# IO_Peripherals.net
KiCad netlist of a schematic drawn in Altium Designer
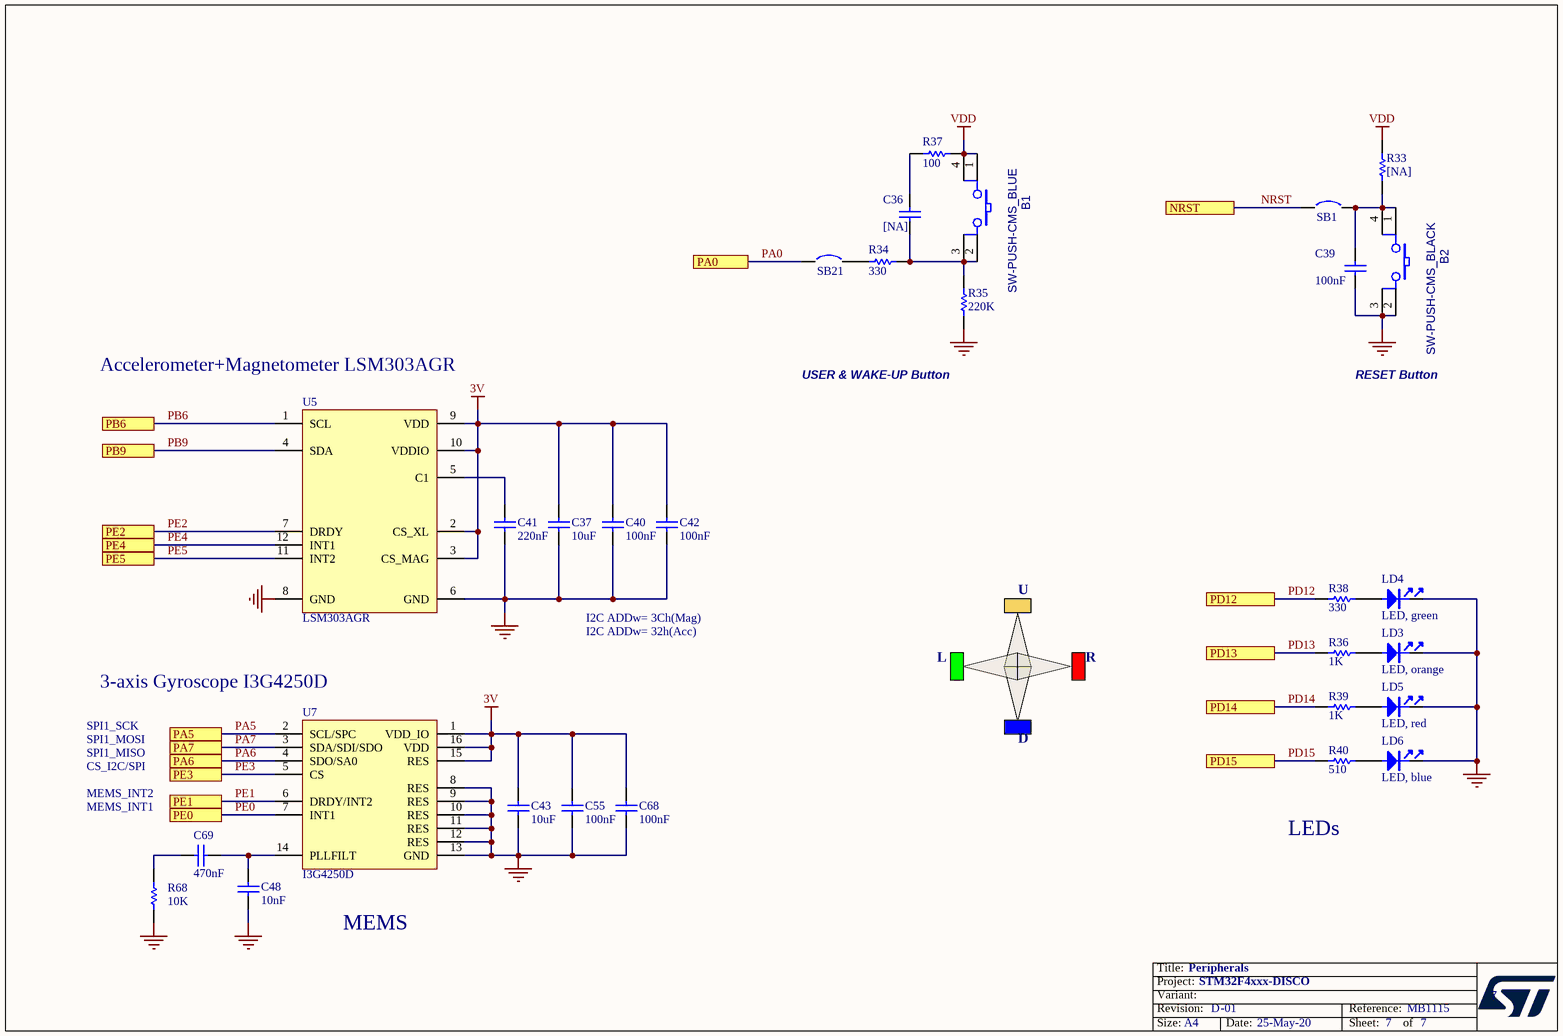
[diagram p0: IO Peripherals.SchDoc]

(export (version "E")
  (design (tool "Eeschema 10.0.6"))
  (components
    (comp (ref "B1")
      (value "SW-PUSH-CMS_BLUE")
      (footprint "BP1CMS (Primary)")
      (description "Non-Open Push-Button 0.1A 24V")
      (libsource (lib "MCD_TOOLS") (part "SW-PUSH-CMS_BLUE"))
    )
    (comp (ref "B2")
      (value "SW-PUSH-CMS_BLACK")
      (footprint "BP1CMS (Primary)")
      (description "Non-Open Push-Button 0.1A 24V")
      (libsource (lib "MCD_TOOLS") (part "SW-PUSH-CMS_BLACK"))
    )
    (comp (ref "C36")
      (value "[NA]")
      (footprint "0402C (Primary)")
      (description "Capacitor,NA,0402")
      (libsource (lib "MCD_TOOLS") (part "Cap_NA_0402"))
    )
    (comp (ref "C37")
      (value "10uF")
      (footprint "0603C (Primary)")
      (description "Capacitor,10uF,6.3V,X5R,20%,0603,YAGEO")
      (libsource (lib "MCD_TOOLS") (part "Cap_10uF_X5R_10%_0603"))
    )
    (comp (ref "C39")
      (value "100nF")
      (footprint "0402C (Primary)")
      (description "Capacitor,100nF,16V,X7R,10%,0402,YAGEO")
      (libsource (lib "MCD_TOOLS") (part "Cap_100nF_X7R_10%_0402"))
    )
    (comp (ref "C40")
      (value "100nF")
      (footprint "0402C (Primary)")
      (description "Capacitor,100nF,16V,X7R,10%,0402,YAGEO")
      (libsource (lib "MCD_TOOLS") (part "Cap_100nF_X7R_10%_0402"))
    )
    (comp (ref "C41")
      (value "220nF")
      (footprint "0603C (Primary)")
      (description "Capacitor,220nF,16V,X7R,10%,0603,YAGEO")
      (libsource (lib "MCD_TOOLS") (part "Cap_220nF_X7R_10%_0603"))
    )
    (comp (ref "C42")
      (value "100nF")
      (footprint "0402C (Primary)")
      (description "Capacitor,100nF,16V,X7R,10%,0402,YAGEO")
      (libsource (lib "MCD_TOOLS") (part "Cap_100nF_X7R_10%_0402"))
    )
    (comp (ref "C43")
      (value "10uF")
      (footprint "0603C (Primary)")
      (description "Capacitor,10uF,6.3V,X5R,20%,0603,YAGEO")
      (libsource (lib "MCD_TOOLS") (part "Cap_10uF_X5R_10%_0603"))
    )
    (comp (ref "C48")
      (value "10nF")
      (footprint "0603C (Primary)")
      (description "Capacitor,10nF,50V,X7R,10%,0603,YAGEO")
      (libsource (lib "MCD_TOOLS") (part "Cap_10nF_X7R_10%_0603"))
    )
    (comp (ref "C55")
      (value "100nF")
      (footprint "0402C (Primary)")
      (description "Capacitor,100nF,16V,X7R,10%,0402,YAGEO")
      (libsource (lib "MCD_TOOLS") (part "Cap_100nF_X7R_10%_0402"))
    )
    (comp (ref "C68")
      (value "100nF")
      (footprint "0402C (Primary)")
      (description "Capacitor,100nF,16V,X7R,10%,0402,YAGEO")
      (libsource (lib "MCD_TOOLS") (part "Cap_100nF_X7R_10%_0402"))
    )
    (comp (ref "C69")
      (value "470nF")
      (footprint "0603C (Primary)")
      (description "Capacitor, MLCC, 470nF, 16V, X7R, 10%, 0603, T=0.8mm")
      (fields
        (field (name "INTERNAL_PART_NUMBER") "MCD-01006")
        (field (name "MANUFACTURER_PART_NUMBER") "CC0603KRX7R7BB474")
        (field (name "PROVIDED_BY") "SUBCO")
      )
      (libsource (lib "MCD_PARTS_database") (part "Capacitor"))
    )
    (comp (ref "LD3")
      (value "LED, orange")
      (footprint "0603D (Primary)")
      (description "LED, orange, 0603")
      (libsource (lib "MCD_TOOLS") (part "LED_orange"))
    )
    (comp (ref "LD4")
      (value "LED, green")
      (footprint "0603D (Primary)")
      (description "LED, green, 0603")
      (libsource (lib "MCD_TOOLS") (part "LED_green"))
    )
    (comp (ref "LD5")
      (value "LED, red")
      (footprint "0603D (Primary)")
      (description "LED, red, 0603")
      (libsource (lib "MCD_TOOLS") (part "LED_red"))
    )
    (comp (ref "LD6")
      (value "LED, blue")
      (footprint "0603D (Primary)")
      (description "LED, blue, 0603")
      (libsource (lib "MCD_TOOLS") (part "LED_blue"))
    )
    (comp (ref "R33")
      (value "[NA]")
      (footprint "0402R (Primary)")
      (description "Resistor,[NA],0402")
      (libsource (lib "MCD_TOOLS") (part "Res_NA_0402"))
    )
    (comp (ref "R34")
      (value "330")
      (footprint "0402R (Primary)")
      (description "Resistor")
      (fields (field (name "PUBLISHER") "Altium Limited"))
      (libsource (lib "Miscellaneous Devices") (part "res1"))
    )
    (comp (ref "R35")
      (value "220K")
      (footprint "0402R (Primary)")
      (description "Resistor")
      (fields (field (name "PUBLISHER") "Altium Limited"))
      (libsource (lib "Miscellaneous Devices") (part "res1"))
    )
    (comp (ref "R36")
      (value "1K")
      (footprint "0402R (Primary)")
      (description "Resistor")
      (fields (field (name "PUBLISHER") "Altium Limited"))
      (libsource (lib "Miscellaneous Devices") (part "Res1"))
    )
    (comp (ref "R37")
      (value "100")
      (footprint "0402R (Primary)")
      (description "Resistor")
      (fields (field (name "PUBLISHER") "Altium Limited"))
      (libsource (lib "Miscellaneous Devices") (part "res1"))
    )
    (comp (ref "R38")
      (value "330")
      (footprint "0402R (Primary)")
      (description "Resistor")
      (fields (field (name "PUBLISHER") "Altium Limited"))
      (libsource (lib "Miscellaneous Devices") (part "Res1"))
    )
    (comp (ref "R39")
      (value "1K")
      (footprint "0402R (Primary)")
      (description "Resistor")
      (fields (field (name "PUBLISHER") "Altium Limited"))
      (libsource (lib "Miscellaneous Devices") (part "Res1"))
    )
    (comp (ref "R40")
      (value "510")
      (footprint "0402R (Primary)")
      (description "Resistor")
      (fields (field (name "PUBLISHER") "Altium Limited"))
      (libsource (lib "Miscellaneous Devices") (part "Res1"))
    )
    (comp (ref "R68")
      (value "10K")
      (footprint "0402R (Primary)")
      (description "Resistor")
      (fields (field (name "PUBLISHER") "Altium Limited"))
      (libsource (lib "Miscellaneous Devices") (part "res1"))
    )
    (comp (ref "SB1")
      (value "Circuit Breaker")
      (footprint "JP2_SMD (Primary)")
      (libsource (lib "MCD_TOOLS") (part "Circuit Breaker"))
    )
    (comp (ref "SB21")
      (value "Circuit Breaker")
      (footprint "JP2_SMD (Primary)")
      (libsource (lib "MCD_TOOLS") (part "Circuit Breaker"))
    )
    (comp (ref "U5")
      (value "LSM303AGR")
      (footprint "ICC_LGA12_2X2_P050")
      (description "3D accelerometer and 3D magnetometer")
      (fields
        (field (name "INTERNAL_PART_NUMBER") "MCD-00709")
        (field (name "MANUFACTURER") "STMICROELECTRONICS")
        (field (name "PROVIDED_BY") "SUBCO with ST control")
      )
      (libsource (lib "MCD_PARTS_database") (part "LSM303AGR"))
    )
    (comp (ref "U7")
      (value "I3G4250D")
      (footprint "ICC_LGA16_4X4_P065_H1P1")
      (description "MEMS motion sensor: 3-axis digital output gyroscope LG4-16 4x4mm")
      (fields
        (field (name "INTERNAL_PART_NUMBER") "MCD-01963")
        (field (name "MANUFACTURER") "STMICROELECTRONICS")
        (field (name "PROVIDED_BY") "SUBCO with ST control")
      )
      (libsource (lib "MCD_PARTS_database") (part "I3G4250D"))
    )
  )
  (nets
    (net (code "1") (name "/NRST") (class "Default")
      (node (ref "SB1") (pin "1") (pinfunction "1_1") (pintype "passive"))
    )
    (net (code "2") (name "/PA0") (class "Default")
      (node (ref "SB21") (pin "1") (pinfunction "1_1") (pintype "passive"))
    )
    (net (code "3") (name "/PA5") (class "Default")
      (node (ref "U7") (pin "2") (pinfunction "SCL/SPC_2") (pintype "passive"))
    )
    (net (code "4") (name "/PA6") (class "Default")
      (node (ref "U7") (pin "4") (pinfunction "SDO/SA0_4") (pintype "passive"))
    )
    (net (code "5") (name "/PA7") (class "Default")
      (node (ref "U7") (pin "3") (pinfunction "SDA/SDI/SDO_3") (pintype "passive"))
    )
    (net (code "6") (name "/PB6") (class "Default")
      (node (ref "U5") (pin "1") (pinfunction "SCL_1") (pintype "passive"))
    )
    (net (code "7") (name "/PB9") (class "Default")
      (node (ref "U5") (pin "4") (pinfunction "SDA_4") (pintype "passive"))
    )
    (net (code "8") (name "/PD12") (class "Default")
      (node (ref "R38") (pin "2") (pinfunction "2_2") (pintype "passive"))
    )
    (net (code "9") (name "/PD13") (class "Default")
      (node (ref "R36") (pin "2") (pinfunction "2_2") (pintype "passive"))
    )
    (net (code "10") (name "/PD14") (class "Default")
      (node (ref "R39") (pin "2") (pinfunction "2_2") (pintype "passive"))
    )
    (net (code "11") (name "/PD15") (class "Default")
      (node (ref "R40") (pin "2") (pinfunction "2_2") (pintype "passive"))
    )
    (net (code "12") (name "/PE0") (class "Default")
      (node (ref "U7") (pin "7") (pinfunction "INT1_7") (pintype "passive"))
    )
    (net (code "13") (name "/PE1") (class "Default")
      (node (ref "U7") (pin "6") (pinfunction "DRDY/INT2_6") (pintype "passive"))
    )
    (net (code "14") (name "/PE2") (class "Default")
      (node (ref "U5") (pin "7") (pinfunction "DRDY_7") (pintype "passive"))
    )
    (net (code "15") (name "/PE3") (class "Default")
      (node (ref "U7") (pin "5") (pinfunction "CS_5") (pintype "passive"))
    )
    (net (code "16") (name "/PE4") (class "Default")
      (node (ref "U5") (pin "12") (pinfunction "INT1_12") (pintype "passive"))
    )
    (net (code "17") (name "/PE5") (class "Default")
      (node (ref "U5") (pin "11") (pinfunction "INT2_11") (pintype "passive"))
    )
    (net (code "18") (name "3V") (class "Default")
      (node (ref "C37") (pin "2") (pinfunction "2_2") (pintype "passive"))
      (node (ref "C40") (pin "2") (pinfunction "2_2") (pintype "passive"))
      (node (ref "C42") (pin "2") (pinfunction "2_2") (pintype "passive"))
      (node (ref "C43") (pin "2") (pinfunction "2_2") (pintype "passive"))
      (node (ref "C55") (pin "2") (pinfunction "2_2") (pintype "passive"))
      (node (ref "C68") (pin "2") (pinfunction "2_2") (pintype "passive"))
      (node (ref "U5") (pin "10") (pinfunction "VDDIO_10") (pintype "passive"))
      (node (ref "U5") (pin "2") (pinfunction "CS_XL_2") (pintype "passive"))
      (node (ref "U5") (pin "3") (pinfunction "CS_MAG_3") (pintype "passive"))
      (node (ref "U5") (pin "9") (pinfunction "VDD_9") (pintype "passive"))
      (node (ref "U7") (pin "1") (pinfunction "VDD_IO_1") (pintype "passive"))
      (node (ref "U7") (pin "15") (pinfunction "RES_15") (pintype "passive"))
      (node (ref "U7") (pin "16") (pinfunction "VDD_16") (pintype "passive"))
    )
    (net (code "19") (name "GND") (class "Default")
      (node (ref "B2") (pin "2") (pinfunction "2_2") (pintype "passive"))
      (node (ref "B2") (pin "3") (pinfunction "3_3") (pintype "passive"))
      (node (ref "C37") (pin "1") (pinfunction "1_1") (pintype "passive"))
      (node (ref "C39") (pin "1") (pinfunction "1_1") (pintype "passive"))
      (node (ref "C40") (pin "1") (pinfunction "1_1") (pintype "passive"))
      (node (ref "C41") (pin "1") (pinfunction "1_1") (pintype "passive"))
      (node (ref "C42") (pin "1") (pinfunction "1_1") (pintype "passive"))
      (node (ref "C43") (pin "1") (pinfunction "1_1") (pintype "passive"))
      (node (ref "C48") (pin "1") (pinfunction "1_1") (pintype "passive"))
      (node (ref "C55") (pin "1") (pinfunction "1_1") (pintype "passive"))
      (node (ref "C68") (pin "1") (pinfunction "1_1") (pintype "passive"))
      (node (ref "LD3") (pin "2") (pintype "passive"))
      (node (ref "LD4") (pin "2") (pintype "passive"))
      (node (ref "LD5") (pin "2") (pintype "passive"))
      (node (ref "LD6") (pin "2") (pintype "passive"))
      (node (ref "R35") (pin "1") (pinfunction "1_1") (pintype "passive"))
      (node (ref "R68") (pin "2") (pinfunction "2_2") (pintype "passive"))
      (node (ref "U5") (pin "6") (pinfunction "GND_6") (pintype "passive"))
      (node (ref "U5") (pin "8") (pinfunction "GND_8") (pintype "passive"))
      (node (ref "U7") (pin "10") (pinfunction "RES_10") (pintype "passive"))
      (node (ref "U7") (pin "11") (pinfunction "RES_11") (pintype "passive"))
      (node (ref "U7") (pin "12") (pinfunction "RES_12") (pintype "passive"))
      (node (ref "U7") (pin "13") (pinfunction "GND_13") (pintype "passive"))
      (node (ref "U7") (pin "8") (pinfunction "RES_8") (pintype "passive"))
      (node (ref "U7") (pin "9") (pinfunction "RES_9") (pintype "passive"))
    )
    (net (code "20") (name "Net-(B1-Pad2)") (class "Default")
      (node (ref "B1") (pin "2") (pinfunction "2_2") (pintype "passive"))
      (node (ref "B1") (pin "3") (pinfunction "3_3") (pintype "passive"))
      (node (ref "C36") (pin "1") (pinfunction "1_1") (pintype "passive"))
      (node (ref "R34") (pin "2") (pinfunction "2_2") (pintype "passive"))
      (node (ref "R35") (pin "2") (pinfunction "2_2") (pintype "passive"))
    )
    (net (code "21") (name "Net-(B2-Pad1)") (class "Default")
      (node (ref "B2") (pin "1") (pinfunction "1_1") (pintype "passive"))
      (node (ref "B2") (pin "4") (pinfunction "4_4") (pintype "passive"))
      (node (ref "C39") (pin "2") (pinfunction "2_2") (pintype "passive"))
      (node (ref "R33") (pin "1") (pinfunction "1_1") (pintype "passive"))
      (node (ref "SB1") (pin "2") (pinfunction "2_2") (pintype "passive"))
    )
    (net (code "22") (name "Net-(C36-Pad2)") (class "Default")
      (node (ref "C36") (pin "2") (pinfunction "2_2") (pintype "passive"))
      (node (ref "R37") (pin "1") (pinfunction "1_1") (pintype "passive"))
    )
    (net (code "23") (name "Net-(C69-Pad2)") (class "Default")
      (node (ref "C69") (pin "2") (pinfunction "2_2") (pintype "passive"))
      (node (ref "R68") (pin "1") (pinfunction "1_1") (pintype "passive"))
    )
    (net (code "24") (name "Net-(LD3-Pad1)") (class "Default")
      (node (ref "LD3") (pin "1") (pintype "passive"))
      (node (ref "R36") (pin "1") (pinfunction "1_1") (pintype "passive"))
    )
    (net (code "25") (name "Net-(LD4-Pad1)") (class "Default")
      (node (ref "LD4") (pin "1") (pintype "passive"))
      (node (ref "R38") (pin "1") (pinfunction "1_1") (pintype "passive"))
    )
    (net (code "26") (name "Net-(LD5-Pad1)") (class "Default")
      (node (ref "LD5") (pin "1") (pintype "passive"))
      (node (ref "R39") (pin "1") (pinfunction "1_1") (pintype "passive"))
    )
    (net (code "27") (name "Net-(LD6-Pad1)") (class "Default")
      (node (ref "LD6") (pin "1") (pintype "passive"))
      (node (ref "R40") (pin "1") (pinfunction "1_1") (pintype "passive"))
    )
    (net (code "28") (name "Net-(R34-Pad1)") (class "Default")
      (node (ref "R34") (pin "1") (pinfunction "1_1") (pintype "passive"))
      (node (ref "SB21") (pin "2") (pinfunction "2_2") (pintype "passive"))
    )
    (net (code "29") (name "Net-(U5-C1)") (class "Default")
      (node (ref "C41") (pin "2") (pinfunction "2_2") (pintype "passive"))
      (node (ref "U5") (pin "5") (pinfunction "C1_5") (pintype "passive"))
    )
    (net (code "30") (name "Net-(U7-PLLFILT)") (class "Default")
      (node (ref "C48") (pin "2") (pinfunction "2_2") (pintype "passive"))
      (node (ref "C69") (pin "1") (pinfunction "1_1") (pintype "passive"))
      (node (ref "U7") (pin "14") (pinfunction "PLLFILT_14") (pintype "passive"))
    )
    (net (code "31") (name "VDD") (class "Default")
      (node (ref "B1") (pin "1") (pinfunction "1_1") (pintype "passive"))
      (node (ref "B1") (pin "4") (pinfunction "4_4") (pintype "passive"))
      (node (ref "R33") (pin "2") (pinfunction "2_2") (pintype "passive"))
      (node (ref "R37") (pin "2") (pinfunction "2_2") (pintype "passive"))
    )
  )
)
